# config-power.net
KiCad netlist of a schematic drawn in Altium Designer
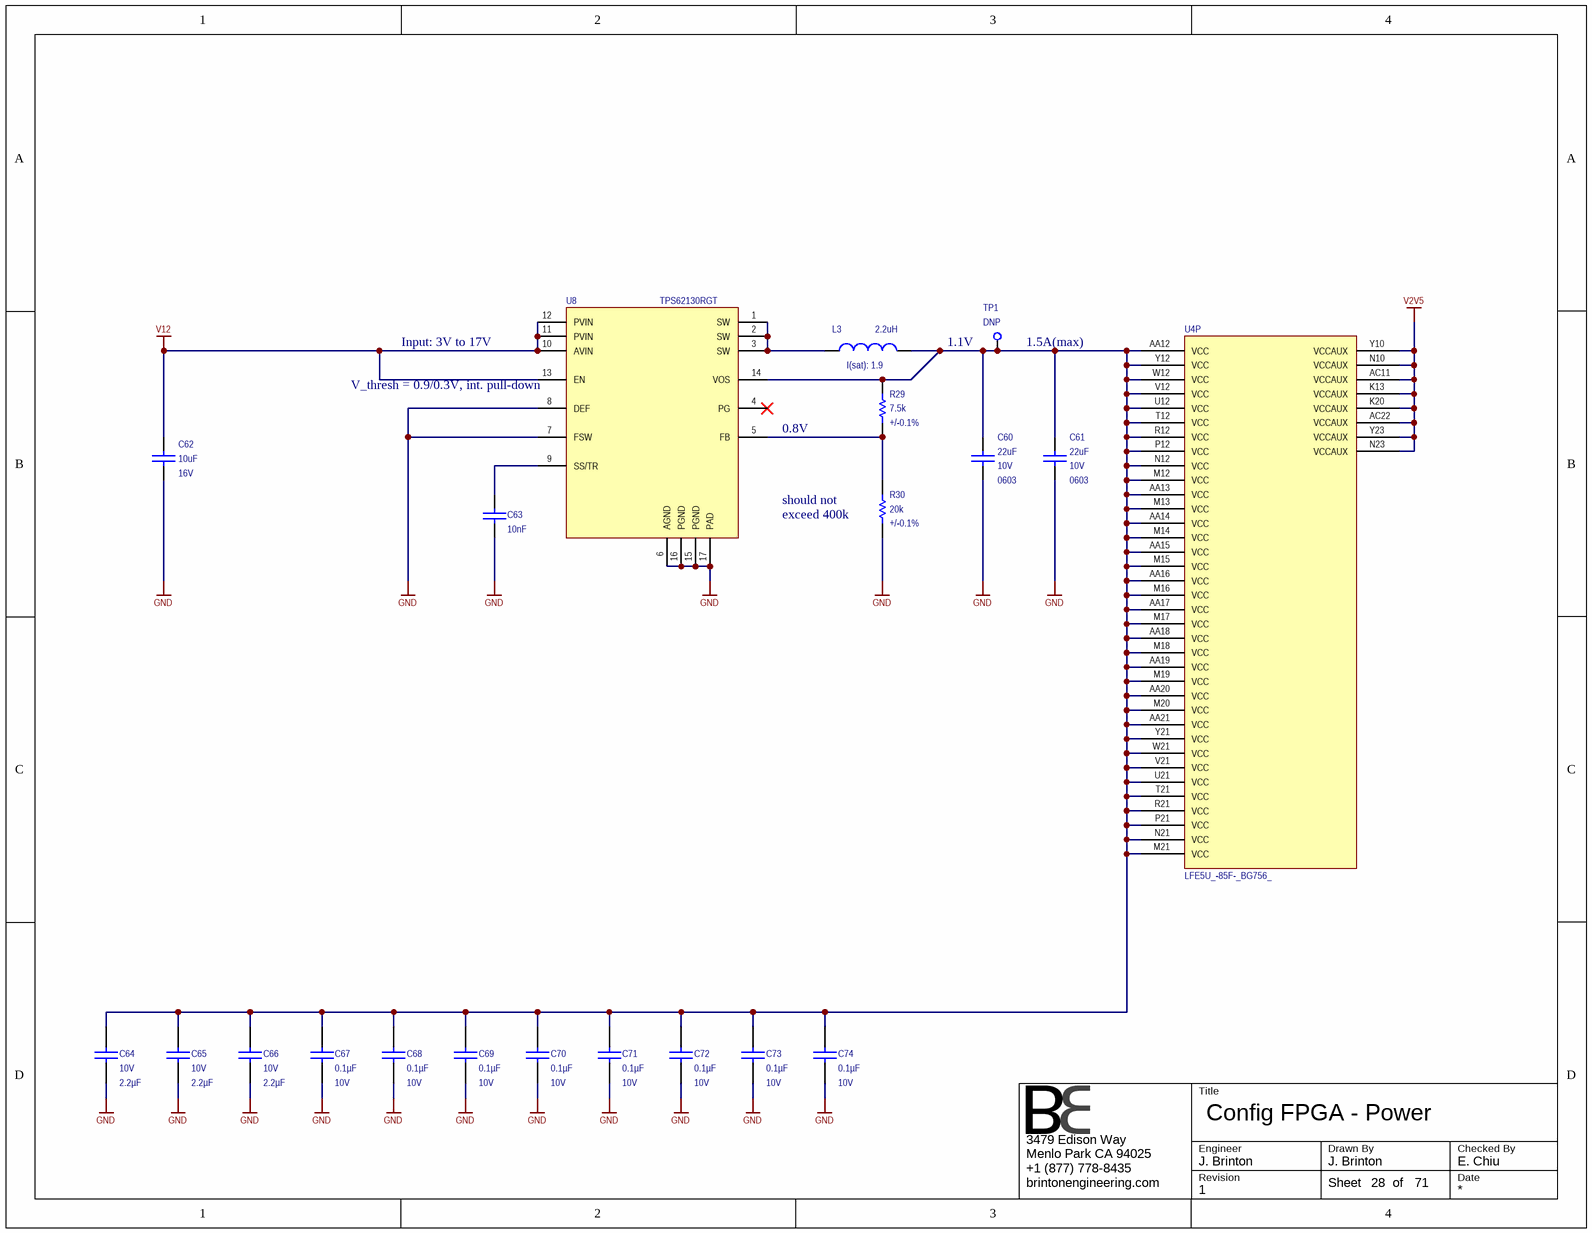
[diagram p0: config-power.SchDoc]

(export (version "E")
  (design (tool "Eeschema 10.0.6"))
  (components
    (comp (ref "C60")
      (value "22uF")
      (footprint "0603")
      (description "Ceramic Capacitor 22uF +/-20% 10V X5R SMD 0603")
      (fields
        (field (name "MANUFACTURER") "TDK Corporation")
        (field (name "TOLERANCE") "+/-20%")
        (field (name "VOLTAGE") "10V")
      )
      (libsource (lib "generic") (part "CAP"))
    )
    (comp (ref "C61")
      (value "22uF")
      (footprint "0603")
      (description "Ceramic Capacitor 22uF +/-20% 10V X5R SMD 0603")
      (fields
        (field (name "MANUFACTURER") "TDK Corporation")
        (field (name "TOLERANCE") "+/-20%")
        (field (name "VOLTAGE") "10V")
      )
      (libsource (lib "generic") (part "CAP"))
    )
    (comp (ref "C62")
      (value "10uF")
      (footprint "0603")
      (description "Ceramic Capacitor 10uF +/-20% 16V X5R 0603")
      (fields
        (field (name "MANUFACTURER") "Taiyo Yuden")
        (field (name "VOLTAGE") "16V")
        (field (name "Comment") "CAP 10UF 0603")
      )
      (libsource (lib "") (part "CAP_1"))
    )
    (comp (ref "C63")
      (value "10nF")
      (footprint "0201")
      (description "Ceramic Capacitor 10nF +/-10% 10V X5R 0201")
      (fields (field (name "MANUFACTURER") "TDK Corporation") (field (name "VOLTAGE") "10V"))
      (libsource (lib "") (part "CAP_1"))
    )
    (comp (ref "C64")
      (value "GRM188R71A225KE15D")
      (footprint "CAPC1608X90N")
      (description "CAP CER 2.2UF 10V 10% X7R 0603")
      (fields
        (field (name "MANUFACTURER") "Murata Electronics North America")
        (field (name "TOLERANCE") "±10%")
        (field (name "VOLTAGE - RATED") "10V")
        (field (name "CAPACITANCE") "2.2µF")
      )
      (libsource (lib "murata") (part "GRM188R71A225KE15D"))
    )
    (comp (ref "C65")
      (value "GRM188R71A225KE15D")
      (footprint "CAPC1608X90N")
      (description "CAP CER 2.2UF 10V 10% X7R 0603")
      (fields
        (field (name "MANUFACTURER") "Murata Electronics North America")
        (field (name "TOLERANCE") "±10%")
        (field (name "VOLTAGE - RATED") "10V")
        (field (name "CAPACITANCE") "2.2µF")
      )
      (libsource (lib "murata") (part "GRM188R71A225KE15D"))
    )
    (comp (ref "C66")
      (value "GRM188R71A225KE15D")
      (footprint "CAPC1608X90N")
      (description "CAP CER 2.2UF 10V 10% X7R 0603")
      (fields
        (field (name "MANUFACTURER") "Murata Electronics North America")
        (field (name "TOLERANCE") "±10%")
        (field (name "VOLTAGE - RATED") "10V")
        (field (name "CAPACITANCE") "2.2µF")
      )
      (libsource (lib "murata") (part "GRM188R71A225KE15D"))
    )
    (comp (ref "C67")
      (value "GRM155R71A104KA01J")
      (footprint "CAPC1005X56N")
      (description "CAP CER 0.1UF 10V 10% X7R 0402")
      (fields
        (field (name "MANUFACTURER") "Murata Electronics North America")
        (field (name "TOLERANCE") "±10%")
        (field (name "CAPACITANCE") "0.1µF")
        (field (name "VOLTAGE - RATED") "10V")
      )
      (libsource (lib "murata") (part "GRM155R71A104KA01J"))
    )
    (comp (ref "C68")
      (value "GRM155R71A104KA01J")
      (footprint "CAPC1005X56N")
      (description "CAP CER 0.1UF 10V 10% X7R 0402")
      (fields
        (field (name "MANUFACTURER") "Murata Electronics North America")
        (field (name "TOLERANCE") "±10%")
        (field (name "CAPACITANCE") "0.1µF")
        (field (name "VOLTAGE - RATED") "10V")
      )
      (libsource (lib "murata") (part "GRM155R71A104KA01J"))
    )
    (comp (ref "C69")
      (value "GRM155R71A104KA01J")
      (footprint "CAPC1005X56N")
      (description "CAP CER 0.1UF 10V 10% X7R 0402")
      (fields
        (field (name "MANUFACTURER") "Murata Electronics North America")
        (field (name "TOLERANCE") "±10%")
        (field (name "CAPACITANCE") "0.1µF")
        (field (name "VOLTAGE - RATED") "10V")
      )
      (libsource (lib "murata") (part "GRM155R71A104KA01J"))
    )
    (comp (ref "C70")
      (value "GRM155R71A104KA01J")
      (footprint "CAPC1005X56N")
      (description "CAP CER 0.1UF 10V 10% X7R 0402")
      (fields
        (field (name "MANUFACTURER") "Murata Electronics North America")
        (field (name "TOLERANCE") "±10%")
        (field (name "CAPACITANCE") "0.1µF")
        (field (name "VOLTAGE - RATED") "10V")
      )
      (libsource (lib "murata") (part "GRM155R71A104KA01J"))
    )
    (comp (ref "C71")
      (value "GRM155R71A104KA01J")
      (footprint "CAPC1005X56N")
      (description "CAP CER 0.1UF 10V 10% X7R 0402")
      (fields
        (field (name "MANUFACTURER") "Murata Electronics North America")
        (field (name "TOLERANCE") "±10%")
        (field (name "CAPACITANCE") "0.1µF")
        (field (name "VOLTAGE - RATED") "10V")
      )
      (libsource (lib "murata") (part "GRM155R71A104KA01J"))
    )
    (comp (ref "C72")
      (value "GRM155R71A104KA01J")
      (footprint "CAPC1005X56N")
      (description "CAP CER 0.1UF 10V 10% X7R 0402")
      (fields
        (field (name "MANUFACTURER") "Murata Electronics North America")
        (field (name "TOLERANCE") "±10%")
        (field (name "CAPACITANCE") "0.1µF")
        (field (name "VOLTAGE - RATED") "10V")
      )
      (libsource (lib "murata") (part "GRM155R71A104KA01J"))
    )
    (comp (ref "C73")
      (value "GRM155R71A104KA01J")
      (footprint "CAPC1005X56N")
      (description "CAP CER 0.1UF 10V 10% X7R 0402")
      (fields
        (field (name "MANUFACTURER") "Murata Electronics North America")
        (field (name "TOLERANCE") "±10%")
        (field (name "CAPACITANCE") "0.1µF")
        (field (name "VOLTAGE - RATED") "10V")
      )
      (libsource (lib "murata") (part "GRM155R71A104KA01J"))
    )
    (comp (ref "C74")
      (value "GRM155R71A104KA01J")
      (footprint "CAPC1005X56N")
      (description "CAP CER 0.1UF 10V 10% X7R 0402")
      (fields
        (field (name "MANUFACTURER") "Murata Electronics North America")
        (field (name "TOLERANCE") "±10%")
        (field (name "CAPACITANCE") "0.1µF")
        (field (name "VOLTAGE - RATED") "10V")
      )
      (libsource (lib "murata") (part "GRM155R71A104KA01J"))
    )
    (comp (ref "L3")
      (value "2.2uH")
      (footprint "ASPI-3010FS")
      (description "Wirewound Inductor 2.2uH +/-20% 1.9A SMD 2518")
      (fields
        (field (name "MANUFACTURER") "Abracon")
        (field (name "I(SAT)") "1.9")
        (field (name "Comment") "ASPI-0310FS-2R2M-T2")
      )
      (libsource (lib "CamBoard_Pico_70.19K") (part "COIL"))
    )
    (comp (ref "R29")
      (value "7.5k")
      (footprint "RESC1608X55N")
      (description "Thick Film Resistor 7.5k Ohms +/-0.1% 0.1W 75V SMD 0603")
      (fields
        (field (name "TOLERANCE") "+/-0.1%")
        (field (name "MANUFACTURER") "Panasonic - ECG")
        (field (name "VOLTAGE") "75V")
      )
      (libsource (lib "brinton") (part "RES"))
    )
    (comp (ref "R30")
      (value "20k")
      (footprint "RESC1608X55N")
      (description "Thick Film Resistor 20k Ohms +/-0.1% 0.1W 75V SMD 0603")
      (fields
        (field (name "TOLERANCE") "+/-0.1%")
        (field (name "MANUFACTURER") "Panasonic - ECG")
        (field (name "VOLTAGE") "75V")
      )
      (libsource (lib "brinton") (part "RES"))
    )
    (comp (ref "TP1")
      (value "TEST_POINT")
      (footprint "TEST_POINT")
      (description "Thruhole Miniature Test Point")
      (fields (field (name "MANUFACTURER") "Keystone Electronics Corp") (field (name "DO NOT PLACE") "DNP"))
      (libsource (lib "generic") (part "TEST_POINT"))
    )
    (comp (ref "U4")
      (value "LFE5U_-85F-_BG756_")
      (footprint "lattice:caBGA756")
      (description "ECP5 FPGA, 85k LUT, 756-caBGA")
      (fields (field (name "MANUFACTURER") "Lattice Semiconductor"))
      (libsource (lib "lattice") (part "LFE5U_-85F-_BG756_"))
    )
    (comp (ref "U8")
      (value "TPS62130RGT")
      (footprint "S-PQFP-8N")
      (description "3-17V 3A Step-Down Converter VQFN")
      (fields (field (name "MANUFACTURER") "Texas Instruments"))
      (libsource (lib "ti") (part "TPS62130RGT"))
    )
  )
  (nets
    (net (code "1") (name "GND") (class "Default")
      (node (ref "C60") (pin "1") (pinfunction "1_1") (pintype "passive"))
      (node (ref "C61") (pin "1") (pinfunction "1_1") (pintype "passive"))
      (node (ref "C62") (pin "1") (pinfunction "1_1") (pintype "passive"))
      (node (ref "C63") (pin "2") (pinfunction "2_2") (pintype "passive"))
      (node (ref "C64") (pin "1") (pinfunction "1_1") (pintype "passive"))
      (node (ref "C65") (pin "1") (pinfunction "1_1") (pintype "passive"))
      (node (ref "C66") (pin "1") (pinfunction "1_1") (pintype "passive"))
      (node (ref "C67") (pin "1") (pinfunction "1_1") (pintype "passive"))
      (node (ref "C68") (pin "1") (pinfunction "1_1") (pintype "passive"))
      (node (ref "C69") (pin "1") (pinfunction "1_1") (pintype "passive"))
      (node (ref "C70") (pin "1") (pinfunction "1_1") (pintype "passive"))
      (node (ref "C71") (pin "1") (pinfunction "1_1") (pintype "passive"))
      (node (ref "C72") (pin "1") (pinfunction "1_1") (pintype "passive"))
      (node (ref "C73") (pin "1") (pinfunction "1_1") (pintype "passive"))
      (node (ref "C74") (pin "1") (pinfunction "1_1") (pintype "passive"))
      (node (ref "R30") (pin "1") (pinfunction "1_1") (pintype "passive"))
      (node (ref "U8") (pin "15") (pinfunction "PGND_15") (pintype "passive"))
      (node (ref "U8") (pin "16") (pinfunction "PGND_16") (pintype "passive"))
      (node (ref "U8") (pin "17") (pinfunction "PAD_17") (pintype "passive"))
      (node (ref "U8") (pin "6") (pinfunction "AGND_6") (pintype "passive"))
      (node (ref "U8") (pin "7") (pinfunction "FSW_7") (pintype "passive"))
      (node (ref "U8") (pin "8") (pinfunction "DEF_8") (pintype "passive"))
    )
    (net (code "2") (name "Net-(L3-Pad1)") (class "Default")
      (node (ref "L3") (pin "1") (pinfunction "1_1") (pintype "passive"))
      (node (ref "U8") (pin "1") (pinfunction "SW_1") (pintype "passive"))
      (node (ref "U8") (pin "2") (pinfunction "SW_2") (pintype "passive"))
      (node (ref "U8") (pin "3") (pinfunction "SW_3") (pintype "passive"))
    )
    (net (code "3") (name "Net-(U8-FB)") (class "Default")
      (node (ref "R29") (pin "1") (pinfunction "1_1") (pintype "passive"))
      (node (ref "R30") (pin "2") (pinfunction "2_2") (pintype "passive"))
      (node (ref "U8") (pin "5") (pinfunction "FB_5") (pintype "passive"))
    )
    (net (code "4") (name "Net-(U8-SS{slash}TR)") (class "Default")
      (node (ref "C63") (pin "1") (pinfunction "1_1") (pintype "passive"))
      (node (ref "U8") (pin "9") (pinfunction "SS/TR_9") (pintype "passive"))
    )
    (net (code "5") (name "Net-(U8-VOS)") (class "Default")
      (node (ref "C60") (pin "2") (pinfunction "2_2") (pintype "passive"))
      (node (ref "C61") (pin "2") (pinfunction "2_2") (pintype "passive"))
      (node (ref "C64") (pin "2") (pinfunction "2_2") (pintype "passive"))
      (node (ref "C65") (pin "2") (pinfunction "2_2") (pintype "passive"))
      (node (ref "C66") (pin "2") (pinfunction "2_2") (pintype "passive"))
      (node (ref "C67") (pin "2") (pinfunction "2_2") (pintype "passive"))
      (node (ref "C68") (pin "2") (pinfunction "2_2") (pintype "passive"))
      (node (ref "C69") (pin "2") (pinfunction "2_2") (pintype "passive"))
      (node (ref "C70") (pin "2") (pinfunction "2_2") (pintype "passive"))
      (node (ref "C71") (pin "2") (pinfunction "2_2") (pintype "passive"))
      (node (ref "C72") (pin "2") (pinfunction "2_2") (pintype "passive"))
      (node (ref "C73") (pin "2") (pinfunction "2_2") (pintype "passive"))
      (node (ref "C74") (pin "2") (pinfunction "2_2") (pintype "passive"))
      (node (ref "L3") (pin "2") (pinfunction "2_2") (pintype "passive"))
      (node (ref "R29") (pin "2") (pinfunction "2_2") (pintype "passive"))
      (node (ref "TP1") (pin "1") (pinfunction "1_1") (pintype "passive"))
      (node (ref "U4") (pin "AA12") (pinfunction "VCC_AA12") (pintype "power_in"))
      (node (ref "U4") (pin "AA13") (pinfunction "VCC_AA13") (pintype "power_in"))
      (node (ref "U4") (pin "AA14") (pinfunction "VCC_AA14") (pintype "power_in"))
      (node (ref "U4") (pin "AA15") (pinfunction "VCC_AA15") (pintype "power_in"))
      (node (ref "U4") (pin "AA16") (pinfunction "VCC_AA16") (pintype "power_in"))
      (node (ref "U4") (pin "AA17") (pinfunction "VCC_AA17") (pintype "power_in"))
      (node (ref "U4") (pin "AA18") (pinfunction "VCC_AA18") (pintype "power_in"))
      (node (ref "U4") (pin "AA19") (pinfunction "VCC_AA19") (pintype "power_in"))
      (node (ref "U4") (pin "AA20") (pinfunction "VCC_AA20") (pintype "power_in"))
      (node (ref "U4") (pin "AA21") (pinfunction "VCC_AA21") (pintype "power_in"))
      (node (ref "U4") (pin "M12") (pinfunction "VCC_M12") (pintype "power_in"))
      (node (ref "U4") (pin "M13") (pinfunction "VCC_M13") (pintype "power_in"))
      (node (ref "U4") (pin "M14") (pinfunction "VCC_M14") (pintype "power_in"))
      (node (ref "U4") (pin "M15") (pinfunction "VCC_M15") (pintype "power_in"))
      (node (ref "U4") (pin "M16") (pinfunction "VCC_M16") (pintype "power_in"))
      (node (ref "U4") (pin "M17") (pinfunction "VCC_M17") (pintype "power_in"))
      (node (ref "U4") (pin "M18") (pinfunction "VCC_M18") (pintype "power_in"))
      (node (ref "U4") (pin "M19") (pinfunction "VCC_M19") (pintype "power_in"))
      (node (ref "U4") (pin "M20") (pinfunction "VCC_M20") (pintype "power_in"))
      (node (ref "U4") (pin "M21") (pinfunction "VCC_M21") (pintype "power_in"))
      (node (ref "U4") (pin "N12") (pinfunction "VCC_N12") (pintype "power_in"))
      (node (ref "U4") (pin "N21") (pinfunction "VCC_N21") (pintype "power_in"))
      (node (ref "U4") (pin "P12") (pinfunction "VCC_P12") (pintype "power_in"))
      (node (ref "U4") (pin "P21") (pinfunction "VCC_P21") (pintype "power_in"))
      (node (ref "U4") (pin "R12") (pinfunction "VCC_R12") (pintype "power_in"))
      (node (ref "U4") (pin "R21") (pinfunction "VCC_R21") (pintype "power_in"))
      (node (ref "U4") (pin "T12") (pinfunction "VCC_T12") (pintype "power_in"))
      (node (ref "U4") (pin "T21") (pinfunction "VCC_T21") (pintype "power_in"))
      (node (ref "U4") (pin "U12") (pinfunction "VCC_U12") (pintype "power_in"))
      (node (ref "U4") (pin "U21") (pinfunction "VCC_U21") (pintype "power_in"))
      (node (ref "U4") (pin "V12") (pinfunction "VCC_V12") (pintype "power_in"))
      (node (ref "U4") (pin "V21") (pinfunction "VCC_V21") (pintype "power_in"))
      (node (ref "U4") (pin "W12") (pinfunction "VCC_W12") (pintype "power_in"))
      (node (ref "U4") (pin "W21") (pinfunction "VCC_W21") (pintype "power_in"))
      (node (ref "U4") (pin "Y12") (pinfunction "VCC_Y12") (pintype "power_in"))
      (node (ref "U4") (pin "Y21") (pinfunction "VCC_Y21") (pintype "power_in"))
      (node (ref "U8") (pin "14") (pinfunction "VOS_14") (pintype "passive"))
    )
    (net (code "6") (name "V2V5") (class "Default")
      (node (ref "U4") (pin "AC11") (pinfunction "VCCAUX_AC11") (pintype "power_in"))
      (node (ref "U4") (pin "AC22") (pinfunction "VCCAUX_AC22") (pintype "power_in"))
      (node (ref "U4") (pin "K13") (pinfunction "VCCAUX_K13") (pintype "power_in"))
      (node (ref "U4") (pin "K20") (pinfunction "VCCAUX_K20") (pintype "power_in"))
      (node (ref "U4") (pin "N10") (pinfunction "VCCAUX_N10") (pintype "power_in"))
      (node (ref "U4") (pin "N23") (pinfunction "VCCAUX_N23") (pintype "power_in"))
      (node (ref "U4") (pin "Y10") (pinfunction "VCCAUX_Y10") (pintype "power_in"))
      (node (ref "U4") (pin "Y23") (pinfunction "VCCAUX_Y23") (pintype "power_in"))
    )
    (net (code "7") (name "V12") (class "Default")
      (node (ref "C62") (pin "2") (pinfunction "2_2") (pintype "passive"))
      (node (ref "U8") (pin "10") (pinfunction "AVIN_10") (pintype "passive"))
      (node (ref "U8") (pin "11") (pinfunction "PVIN_11") (pintype "passive"))
      (node (ref "U8") (pin "12") (pinfunction "PVIN_12") (pintype "passive"))
      (node (ref "U8") (pin "13") (pinfunction "EN_13") (pintype "passive"))
    )
    (net (code "8") (name "unconnected-(U8-PG-Pad4)") (class "Default")
      (node (ref "U8") (pin "4") (pinfunction "PG_4") (pintype "passive+no_connect"))
    )
  )
)
